# EG2131.net
KiCad netlist of a schematic drawn in Altium Designer
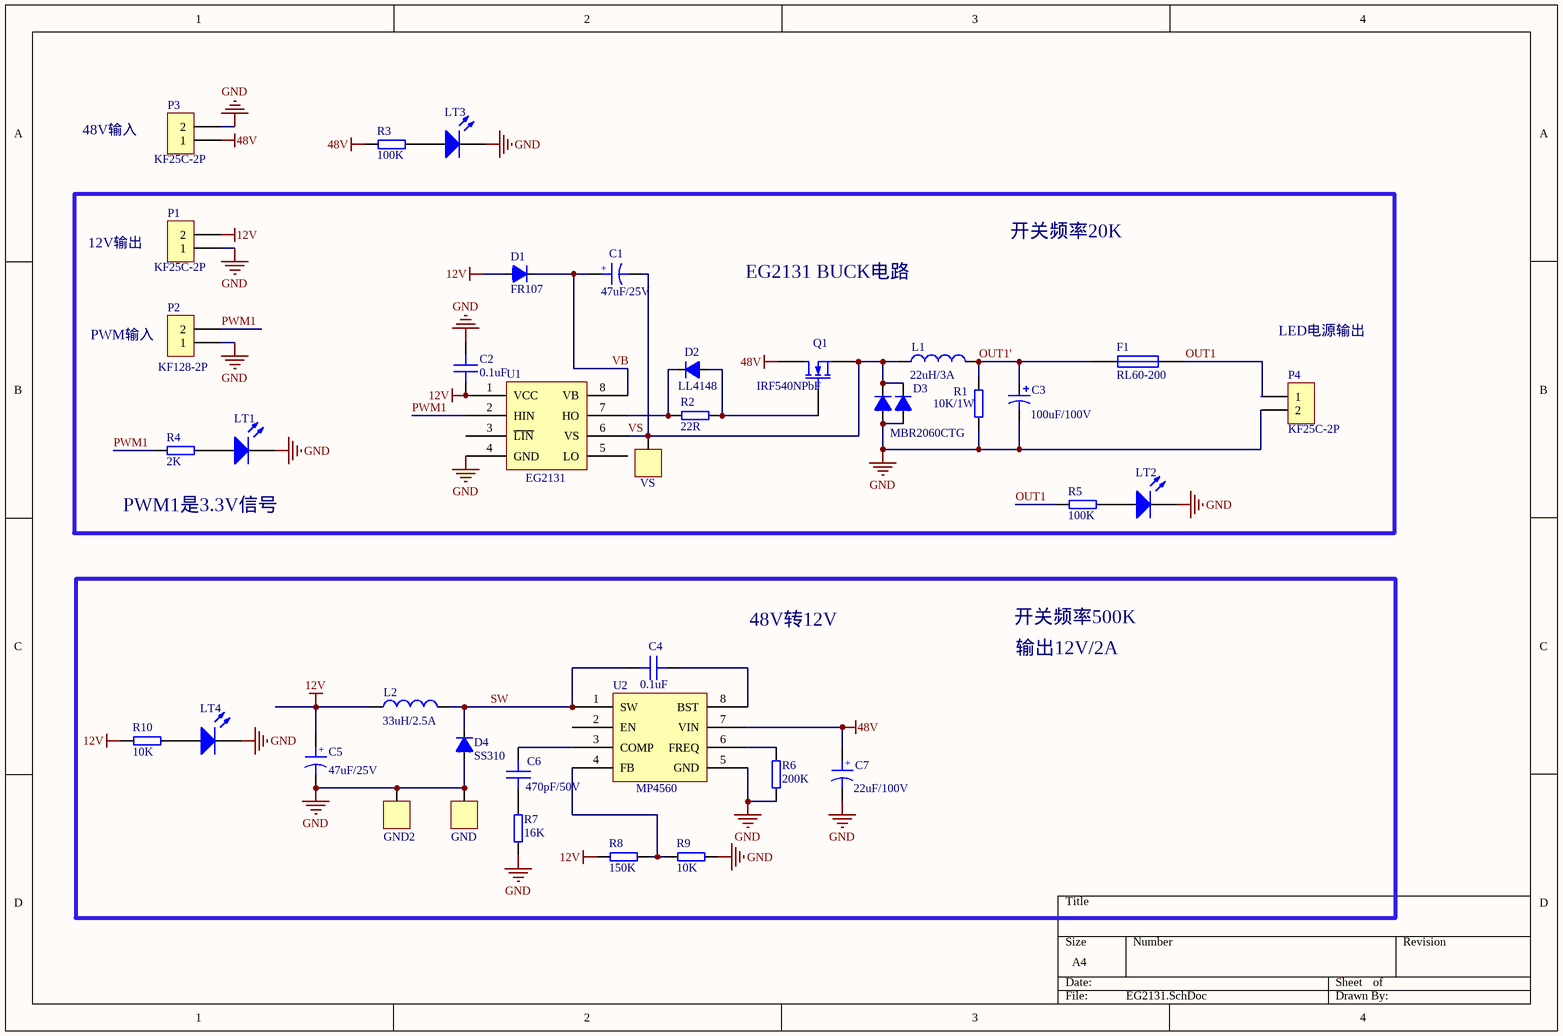
[diagram p0: EG2131.SchDoc]

(export (version "E")
  (design (tool "Eeschema 10.0.6"))
  (components
    (comp (ref "C1")
      (value "47uF/25V")
      (footprint "CAP2MM")
      (description "电解电容")
      (fields (field (name "TOLERANCE") "20%") (field (name "VOLTAGE") "25V"))
      (libsource (lib "Sungrow") (part "Capactior - Po polarized"))
    )
    (comp (ref "C2")
      (value "0.1uF")
      (footprint "0805")
      (description "贴片电容")
      (fields (field (name "TOLERANCE") "10%") (field (name "VOLTAGE") "50V"))
      (libsource (lib "AD_Lib") (part "Capacitor _non polarized_chip"))
    )
    (comp (ref "C3")
      (value "100uF/100V")
      (footprint "CAP5MM")
      (description "电解电容")
      (fields
        (field (name "Comment") "100V-YXJ-100uF-M 10X20，Rubycon")
        (field (name "PUBLISHER") "Altium Limited")
      )
      (libsource (lib "Miscellaneous Devices") (part "Cap Pol1"))
    )
    (comp (ref "C4")
      (value "0.1uF")
      (footprint "0805")
      (description "贴片电容")
      (fields (field (name "TOLERANCE") "10%") (field (name "VOLTAGE") "50V"))
      (libsource (lib "AD_Lib") (part "Capacitor _non polarized_chip"))
    )
    (comp (ref "C5")
      (value "47uF/25V")
      (footprint "CAP2MM")
      (description "电解电容")
      (fields (field (name "TOLERANCE") "20%") (field (name "VOLTAGE") "25V"))
      (libsource (lib "Sungrow") (part "Capactior - Po polarized"))
    )
    (comp (ref "C6")
      (value "470pF/50V")
      (footprint "0805")
      (description "贴片电容")
      (fields (field (name "TOLERANCE") "10%") (field (name "VOLTAGE") "50V"))
      (libsource (lib "AD_Lib") (part "Capacitor _non polarized_chip"))
    )
    (comp (ref "C7")
      (value "22uF/100V")
      (footprint "CAP2.5MM")
      (description "电解电容")
      (fields (field (name "TOLERANCE") "20%") (field (name "VOLTAGE") "25V"))
      (libsource (lib "Sungrow") (part "Capactior - Po polarized"))
    )
    (comp (ref "D1")
      (value "FR107")
      (footprint "DO-41-3.8")
      (description "二极管")
      (fields (field (name "Comment") "FR107，MDD"))
      (libsource (lib "CONTROLV1.1") (part "1N4148"))
    )
    (comp (ref "D2")
      (value "LL4148")
      (footprint "LL4148")
      (description "二极管")
      (fields (field (name "Comment") "LL4148,，MDD"))
      (libsource (lib "CONTROLV1.1") (part "1N4148"))
    )
    (comp (ref "D3")
      (value "MBR2060CTG")
      (footprint "TO220-HS-2P")
      (description "二极管")
      (fields (field (name "Comment") "MBR2060CTG，ON"))
      (libsource (lib "CONTROLV1.1") (part "MBR2060"))
    )
    (comp (ref "D4")
      (value "SS310")
      (footprint "SMC")
      (description "二极管")
      (fields (field (name "Comment") "SS310，MDD"))
      (libsource (lib "CONTROLV1.1") (part "1N4148"))
    )
    (comp (ref "F1")
      (value "RL60-200")
      (footprint "RL60-110")
      (description "保险丝")
      (fields (field (name "Comment") "RL60-200，瑞隆源") (field (name "PUBLISHER") "Altium Limited"))
      (libsource (lib "Miscellaneous Devices") (part "Fuse 1"))
    )
    (comp (ref "GND")
      (value "Testpoint")
      (footprint "TEST")
      (description "测试点")
      (libsource (lib "CONTROLV1.1") (part "Testpoint"))
    )
    (comp (ref "GND2")
      (value "Testpoint")
      (footprint "TEST")
      (description "测试点")
      (libsource (lib "CONTROLV1.1") (part "Testpoint"))
    )
    (comp (ref "L1")
      (value "22uH/3A")
      (footprint "L_6.6*7.0")
      (description "功率电感")
      (fields (field (name "Comment") "MWSA0603S-220MT，顺络") (field (name "PUBLISHER") "Altium Limited"))
      (libsource (lib "Miscellaneous Devices") (part "Inductor"))
    )
    (comp (ref "L2")
      (value "33uH/2.5A")
      (footprint "L_6.6*7.0")
      (description "功率电感")
      (fields (field (name "Comment") "MWSA0603S-330MT，顺络") (field (name "PUBLISHER") "Altium Limited"))
      (libsource (lib "Miscellaneous Devices") (part "Inductor"))
    )
    (comp (ref "LT1")
      (value "红，0805")
      (footprint "led0805")
      (description "发光二极管")
      (fields (field (name "PUBLISHER") "Altium Limited"))
      (libsource (lib "Miscellaneous Devices") (part "LED2"))
    )
    (comp (ref "LT2")
      (value "红，0805")
      (footprint "led0805")
      (description "发光二极管")
      (fields (field (name "PUBLISHER") "Altium Limited"))
      (libsource (lib "Miscellaneous Devices") (part "LED2"))
    )
    (comp (ref "LT3")
      (value "红，0805")
      (footprint "led0805")
      (description "发光二极管")
      (fields (field (name "PUBLISHER") "Altium Limited"))
      (libsource (lib "Miscellaneous Devices") (part "LED2"))
    )
    (comp (ref "LT4")
      (value "红，0805")
      (footprint "led0805")
      (description "发光二极管")
      (fields (field (name "PUBLISHER") "Altium Limited"))
      (libsource (lib "Miscellaneous Devices") (part "LED2"))
    )
    (comp (ref "P1")
      (value "KF25C-2P")
      (footprint "KF25C-2P")
      (description "栅栏式接线端子")
      (fields (field (name "Comment") "KF25C-2P ，间距7.62MM"))
      (libsource (lib "CONTROLV1.1") (part "Header 2"))
    )
    (comp (ref "P2")
      (value "KF128-2P")
      (footprint "KF128-2P")
      (description "螺钉式PCB端子")
      (fields (field (name "Comment") "KF128-2P ,间距5.08"))
      (libsource (lib "CONTROLV1.1") (part "Header 2"))
    )
    (comp (ref "P3")
      (value "KF25C-2P")
      (footprint "KF25C-2P")
      (description "栅栏式接线端子")
      (fields (field (name "Comment") "KF25C-2P ，间距7.62MM"))
      (libsource (lib "CONTROLV1.1") (part "Header 2"))
    )
    (comp (ref "P4")
      (value "KF25C-2P")
      (footprint "KF25C-2P")
      (description "栅栏式接线端子")
      (fields (field (name "Comment") "KF25C-2P ，间距7.62MM"))
      (libsource (lib "") (part "Header 2_1"))
    )
    (comp (ref "Q1")
      (value "IRF540NPbF")
      (footprint "TO220-HS-2P")
      (description "MOSFET")
      (fields (field (name "Comment") "IRF540NPbF，英飞凌"))
      (libsource (lib "Miscellaneous Devices") (part "MOSFET-N"))
    )
    (comp (ref "R1")
      (value "10K/1W")
      (footprint "1w")
      (description "金属氧化膜电阻")
      (fields (field (name "POWER") "1/10W") (field (name "TOLERANCE") "1%"))
      (libsource (lib "Sungrow") (part "Resistor1"))
    )
    (comp (ref "R2")
      (value "22R")
      (footprint "1206")
      (description "贴片电阻")
      (fields (field (name "POWER") "1/10W") (field (name "TOLERANCE") "1%"))
      (libsource (lib "Sungrow") (part "Resistor1"))
    )
    (comp (ref "R3")
      (value "100K")
      (footprint "0805")
      (description "贴片电阻")
      (fields (field (name "POWER") "1/10W") (field (name "TOLERANCE") "1%"))
      (libsource (lib "Sungrow") (part "Resistor1"))
    )
    (comp (ref "R4")
      (value "2K")
      (footprint "0805")
      (description "贴片电阻")
      (fields (field (name "POWER") "1/10W") (field (name "TOLERANCE") "1%"))
      (libsource (lib "Sungrow") (part "Resistor1"))
    )
    (comp (ref "R5")
      (value "100K")
      (footprint "0805")
      (description "贴片电阻")
      (fields (field (name "POWER") "1/10W") (field (name "TOLERANCE") "1%"))
      (libsource (lib "Sungrow") (part "Resistor1"))
    )
    (comp (ref "R6")
      (value "200K")
      (footprint "0805")
      (description "贴片电阻")
      (fields (field (name "POWER") "1/10W") (field (name "TOLERANCE") "1%"))
      (libsource (lib "Sungrow") (part "Resistor1"))
    )
    (comp (ref "R7")
      (value "16K")
      (footprint "0805")
      (description "贴片电阻")
      (fields (field (name "POWER") "1/10W") (field (name "TOLERANCE") "1%"))
      (libsource (lib "Sungrow") (part "Resistor1"))
    )
    (comp (ref "R8")
      (value "150K")
      (footprint "0805")
      (description "贴片电阻")
      (fields (field (name "POWER") "1/10W") (field (name "TOLERANCE") "1%"))
      (libsource (lib "Sungrow") (part "Resistor1"))
    )
    (comp (ref "R9")
      (value "10K")
      (footprint "0805")
      (description "贴片电阻")
      (fields (field (name "POWER") "1/10W") (field (name "TOLERANCE") "1%"))
      (libsource (lib "Sungrow") (part "Resistor1"))
    )
    (comp (ref "R10")
      (value "10K")
      (footprint "0805")
      (description "贴片电阻")
      (fields (field (name "POWER") "1/10W") (field (name "TOLERANCE") "1%"))
      (libsource (lib "Sungrow") (part "Resistor1"))
    )
    (comp (ref "U1")
      (value "EG2131")
      (footprint "SO-8")
      (description "芯片")
      (libsource (lib "CONTROLV1.1") (part "EG2131"))
    )
    (comp (ref "U2")
      (value "MP4560")
      (footprint "SO-8-MP4560")
      (description "DCDC芯片")
      (fields (field (name "Comment") "MP4560DN，MPS"))
      (libsource (lib "CONTROLV1.1") (part "MP4560"))
    )
    (comp (ref "VS")
      (value "Testpoint")
      (footprint "TEST")
      (description "测试点")
      (libsource (lib "CONTROLV1.1") (part "Testpoint"))
    )
  )
  (nets
    (net (code "1") (name "/OUT1") (class "Default")
      (node (ref "F1") (pin "2") (pinfunction "2_2") (pintype "passive"))
      (node (ref "P4") (pin "1") (pinfunction "1_1") (pintype "passive"))
      (node (ref "R5") (pin "2") (pinfunction "2_2") (pintype "passive"))
    )
    (net (code "2") (name "/OUT1'") (class "Default")
      (node (ref "C3") (pin "1") (pinfunction "1_1") (pintype "passive"))
      (node (ref "F1") (pin "1") (pinfunction "1_1") (pintype "passive"))
      (node (ref "L1") (pin "2") (pinfunction "2_2") (pintype "passive"))
      (node (ref "R1") (pin "2") (pinfunction "2_2") (pintype "passive"))
    )
    (net (code "3") (name "/PWM1") (class "Default")
      (node (ref "P2") (pin "2") (pinfunction "2_2") (pintype "passive"))
      (node (ref "R4") (pin "2") (pinfunction "2_2") (pintype "passive"))
      (node (ref "U1") (pin "2") (pinfunction "HIN_2") (pintype "passive"))
    )
    (net (code "4") (name "/SW") (class "Default")
      (node (ref "C4") (pin "1") (pinfunction "1_1") (pintype "passive"))
      (node (ref "D4") (pin "2") (pinfunction "2_2") (pintype "passive"))
      (node (ref "L2") (pin "2") (pinfunction "2_2") (pintype "passive"))
      (node (ref "U2") (pin "1") (pinfunction "SW_1") (pintype "passive"))
    )
    (net (code "5") (name "/VB") (class "Default")
      (node (ref "C1") (pin "1") (pinfunction "1_1") (pintype "passive"))
      (node (ref "D1") (pin "2") (pinfunction "2_2") (pintype "passive"))
      (node (ref "U1") (pin "8") (pinfunction "VB_8") (pintype "passive"))
    )
    (net (code "6") (name "/VS") (class "Default")
      (node (ref "C1") (pin "2") (pinfunction "2_2") (pintype "passive"))
      (node (ref "D3") (pin "2") (pinfunction "K_2") (pintype "passive"))
      (node (ref "L1") (pin "1") (pinfunction "1_1") (pintype "passive"))
      (node (ref "Q1") (pin "3") (pinfunction "S_3") (pintype "passive"))
      (node (ref "U1") (pin "6") (pinfunction "VS_6") (pintype "passive"))
      (node (ref "VS") (pin "1") (pintype "passive"))
    )
    (net (code "7") (name "12V") (class "Default")
      (node (ref "C2") (pin "1") (pinfunction "1_1") (pintype "passive"))
      (node (ref "C5") (pin "1") (pinfunction "1_1") (pintype "passive"))
      (node (ref "D1") (pin "1") (pinfunction "1_1") (pintype "passive"))
      (node (ref "L2") (pin "1") (pinfunction "1_1") (pintype "passive"))
      (node (ref "P1") (pin "2") (pinfunction "2_2") (pintype "passive"))
      (node (ref "R10") (pin "2") (pinfunction "2_2") (pintype "passive"))
      (node (ref "R8") (pin "2") (pinfunction "2_2") (pintype "passive"))
      (node (ref "U1") (pin "1") (pinfunction "VCC_1") (pintype "passive"))
    )
    (net (code "8") (name "48V") (class "Default")
      (node (ref "C7") (pin "1") (pinfunction "1_1") (pintype "passive"))
      (node (ref "P3") (pin "1") (pinfunction "1_1") (pintype "passive"))
      (node (ref "Q1") (pin "2") (pinfunction "D_2") (pintype "passive"))
      (node (ref "R3") (pin "2") (pinfunction "2_2") (pintype "passive"))
      (node (ref "U2") (pin "7") (pinfunction "VIN_7") (pintype "passive"))
    )
    (net (code "9") (name "GND") (class "Default")
      (node (ref "C2") (pin "2") (pinfunction "2_2") (pintype "passive"))
      (node (ref "C3") (pin "2") (pinfunction "2_2") (pintype "passive"))
      (node (ref "C5") (pin "2") (pinfunction "2_2") (pintype "passive"))
      (node (ref "C7") (pin "2") (pinfunction "2_2") (pintype "passive"))
      (node (ref "D3") (pin "1") (pinfunction "A_1") (pintype "passive"))
      (node (ref "D3") (pin "3") (pinfunction "A_3") (pintype "passive"))
      (node (ref "D4") (pin "1") (pinfunction "1_1") (pintype "passive"))
      (node (ref "GND") (pin "1") (pintype "passive"))
      (node (ref "GND2") (pin "1") (pintype "passive"))
      (node (ref "LT1") (pin "2") (pinfunction "K_2") (pintype "passive"))
      (node (ref "LT2") (pin "2") (pinfunction "K_2") (pintype "passive"))
      (node (ref "LT3") (pin "2") (pinfunction "K_2") (pintype "passive"))
      (node (ref "LT4") (pin "2") (pinfunction "K_2") (pintype "passive"))
      (node (ref "P1") (pin "1") (pinfunction "1_1") (pintype "passive"))
      (node (ref "P2") (pin "1") (pinfunction "1_1") (pintype "passive"))
      (node (ref "P3") (pin "2") (pinfunction "2_2") (pintype "passive"))
      (node (ref "P4") (pin "2") (pinfunction "2_2") (pintype "passive"))
      (node (ref "R1") (pin "1") (pinfunction "1_1") (pintype "passive"))
      (node (ref "R6") (pin "2") (pinfunction "2_2") (pintype "passive"))
      (node (ref "R7") (pin "2") (pinfunction "2_2") (pintype "passive"))
      (node (ref "R9") (pin "1") (pinfunction "1_1") (pintype "passive"))
      (node (ref "U1") (pin "4") (pinfunction "GND_4") (pintype "passive"))
      (node (ref "U2") (pin "5") (pinfunction "GND_5") (pintype "passive"))
    )
    (net (code "10") (name "Net-(C6-Pad1)") (class "Default")
      (node (ref "C6") (pin "1") (pinfunction "1_1") (pintype "passive"))
      (node (ref "R7") (pin "1") (pinfunction "1_1") (pintype "passive"))
    )
    (net (code "11") (name "Net-(LT1-A)") (class "Default")
      (node (ref "LT1") (pin "1") (pinfunction "A_1") (pintype "passive"))
      (node (ref "R4") (pin "1") (pinfunction "1_1") (pintype "passive"))
    )
    (net (code "12") (name "Net-(LT2-A)") (class "Default")
      (node (ref "LT2") (pin "1") (pinfunction "A_1") (pintype "passive"))
      (node (ref "R5") (pin "1") (pinfunction "1_1") (pintype "passive"))
    )
    (net (code "13") (name "Net-(LT3-A)") (class "Default")
      (node (ref "LT3") (pin "1") (pinfunction "A_1") (pintype "passive"))
      (node (ref "R3") (pin "1") (pinfunction "1_1") (pintype "passive"))
    )
    (net (code "14") (name "Net-(LT4-A)") (class "Default")
      (node (ref "LT4") (pin "1") (pinfunction "A_1") (pintype "passive"))
      (node (ref "R10") (pin "1") (pinfunction "1_1") (pintype "passive"))
    )
    (net (code "15") (name "Net-(Q1-G)") (class "Default")
      (node (ref "D2") (pin "1") (pinfunction "1_1") (pintype "passive"))
      (node (ref "Q1") (pin "1") (pinfunction "G_1") (pintype "passive"))
      (node (ref "R2") (pin "2") (pinfunction "2_2") (pintype "passive"))
    )
    (net (code "16") (name "Net-(U1-HO)") (class "Default")
      (node (ref "D2") (pin "2") (pinfunction "2_2") (pintype "passive"))
      (node (ref "R2") (pin "1") (pinfunction "1_1") (pintype "passive"))
      (node (ref "U1") (pin "7") (pinfunction "HO_7") (pintype "passive"))
    )
    (net (code "17") (name "Net-(U2-BST)") (class "Default")
      (node (ref "C4") (pin "2") (pinfunction "2_2") (pintype "passive"))
      (node (ref "U2") (pin "8") (pinfunction "BST_8") (pintype "passive"))
    )
    (net (code "18") (name "Net-(U2-COMP)") (class "Default")
      (node (ref "C6") (pin "2") (pinfunction "2_2") (pintype "passive"))
      (node (ref "U2") (pin "3") (pinfunction "COMP_3") (pintype "passive"))
    )
    (net (code "19") (name "Net-(U2-FB)") (class "Default")
      (node (ref "R8") (pin "1") (pinfunction "1_1") (pintype "passive"))
      (node (ref "R9") (pin "2") (pinfunction "2_2") (pintype "passive"))
      (node (ref "U2") (pin "4") (pinfunction "FB_4") (pintype "passive"))
    )
    (net (code "20") (name "Net-(U2-FREQ)") (class "Default")
      (node (ref "R6") (pin "1") (pinfunction "1_1") (pintype "passive"))
      (node (ref "U2") (pin "6") (pinfunction "FREQ_6") (pintype "passive"))
    )
    (net (code "21") (name "unconnected-(U1-LO-Pad5)") (class "Default")
      (node (ref "U1") (pin "5") (pinfunction "LO_5") (pintype "passive"))
    )
    (net (code "22") (name "unconnected-(U1-~{LIN}-Pad3)") (class "Default")
      (node (ref "U1") (pin "3") (pinfunction "~{LIN}_3") (pintype "passive"))
    )
    (net (code "23") (name "unconnected-(U2-EN-Pad2)") (class "Default")
      (node (ref "U2") (pin "2") (pinfunction "EN_2") (pintype "passive"))
    )
  )
)
